# VirtualKeyBoradMouse_2020-04-23_12-54-09.net
KiCad netlist of a schematic drawn in Altium Designer
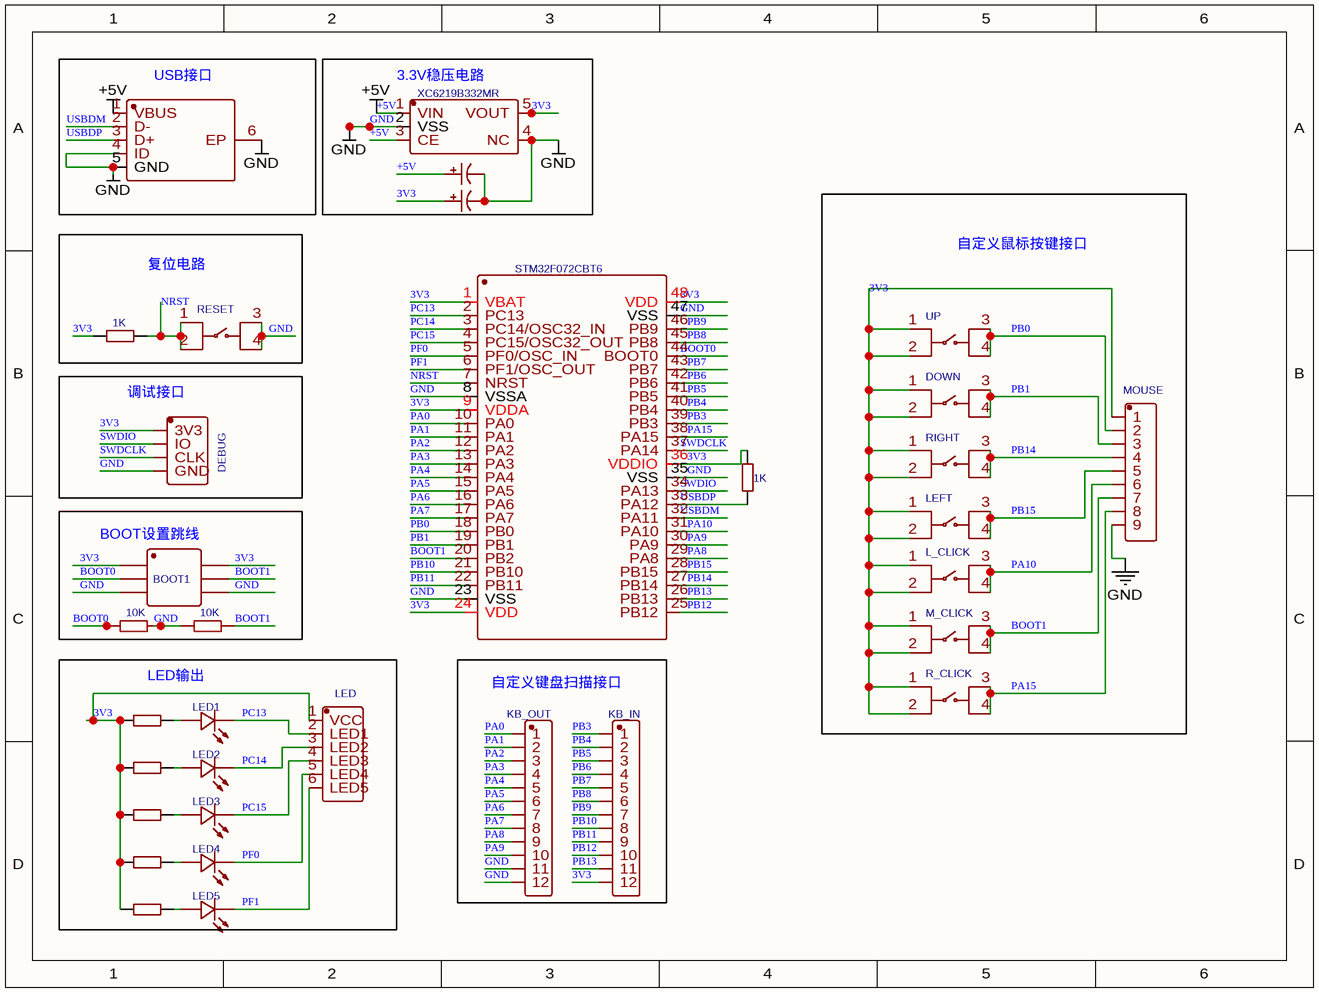
[diagram p0: VirtualKeyBoradMouse_2020-04-23_12-54-09.schdoc]

(export (version "E")
  (design (tool "Eeschema 10.0.6"))
  (components
    (comp (ref "BOOT1")
      (value "210S-2*3P L=11.6MMGold-plated black")
      (fields (field (name "BOM_SUPPLIER PART") "C124384") (field (name "CONTRIBUTOR") "LCSC"))
      (libsource (lib "altium-import") (part "root_0_210S-2*3P L=11.6MMGold-plated black_"))
    )
    (comp (ref "C1")
      (value "100uF")
      (fields
        (field (name "BOM_MANUFACTURER PART") "RVT1A101M0505")
        (field (name "BOM_SUPPLIER PART") "C3347")
      )
      (libsource (lib "altium-import") (part "root_1_100uF_"))
    )
    (comp (ref "C2")
      (value "100uF")
      (fields
        (field (name "BOM_MANUFACTURER PART") "RVT1A101M0505")
        (field (name "BOM_SUPPLIER PART") "C3347")
      )
      (libsource (lib "altium-import") (part "root_1_100uF_"))
    )
    (comp (ref "DEBUG")
      (value "MTP125-1104S1")
      (fields (field (name "BOM_SUPPLIER PART") "C358686") (field (name "CONTRIBUTOR") "LCSC"))
      (libsource (lib "altium-import") (part "root_0_MTP125-1104S1_"))
    )
    (comp (ref "DOWN")
      (value "K2-6639SP-C4SC-04")
      (fields (field (name "BOM_SUPPLIER PART") "C83206"))
      (libsource (lib "altium-import") (part "root_0_K2-6639SP-C4SC-04_"))
    )
    (comp (ref "KB_IN")
      (value "C247920")
      (fields (field (name "CONTRIBUTOR") "LCSC"))
      (libsource (lib "altium-import") (part "root_0_C247920_"))
    )
    (comp (ref "KB_OUT")
      (value "C247920")
      (fields (field (name "CONTRIBUTOR") "LCSC"))
      (libsource (lib "altium-import") (part "root_0_C247920_"))
    )
    (comp (ref "LED")
      (value "210S-1*6P L=11.6MMGold-plated black")
      (fields (field (name "BOM_SUPPLIER PART") "C124380") (field (name "CONTRIBUTOR") "LCSC"))
      (libsource (lib "altium-import") (part "root_0_210S-1*6P L=11.6MMGold-plated black_"))
    )
    (comp (ref "LED1")
      (value "NCD0603R5")
      (fields (field (name "BOM_SUPPLIER PART") "C193902") (field (name "CONTRIBUTOR") "LCSC"))
      (libsource (lib "altium-import") (part "root_2_NCD0603R5_"))
    )
    (comp (ref "LED2")
      (value "NCD0603R5")
      (fields (field (name "BOM_SUPPLIER PART") "C193902") (field (name "CONTRIBUTOR") "LCSC"))
      (libsource (lib "altium-import") (part "root_2_NCD0603R5_"))
    )
    (comp (ref "LED3")
      (value "NCD0603R5")
      (fields (field (name "BOM_SUPPLIER PART") "C193902") (field (name "CONTRIBUTOR") "LCSC"))
      (libsource (lib "altium-import") (part "root_2_NCD0603R5_"))
    )
    (comp (ref "LED4")
      (value "NCD0603R5")
      (fields (field (name "BOM_SUPPLIER PART") "C193902") (field (name "CONTRIBUTOR") "LCSC"))
      (libsource (lib "altium-import") (part "root_2_NCD0603R5_"))
    )
    (comp (ref "LED5")
      (value "NCD0603R5")
      (fields (field (name "BOM_SUPPLIER PART") "C193902") (field (name "CONTRIBUTOR") "LCSC"))
      (libsource (lib "altium-import") (part "root_2_NCD0603R5_"))
    )
    (comp (ref "LEFT")
      (value "K2-6639SP-C4SC-04")
      (fields (field (name "BOM_SUPPLIER PART") "C83206"))
      (libsource (lib "altium-import") (part "root_0_K2-6639SP-C4SC-04_"))
    )
    (comp (ref "L_CLICK")
      (value "K2-6639SP-C4SC-04")
      (fields (field (name "BOM_SUPPLIER PART") "C83206"))
      (libsource (lib "altium-import") (part "root_0_K2-6639SP-C4SC-04_"))
    )
    (comp (ref "MOUSE")
      (value "220S-1*9P H=8.5MM Ytype Gold-plated")
      (fields (field (name "BOM_SUPPLIER PART") "C124417") (field (name "CONTRIBUTOR") "LCSC"))
      (libsource (lib "altium-import") (part "root_0_220S-1*9P H=8.5MM Ytype Gold-plated_"))
    )
    (comp (ref "M_CLICK")
      (value "K2-6639SP-C4SC-04")
      (fields (field (name "BOM_SUPPLIER PART") "C83206"))
      (libsource (lib "altium-import") (part "root_0_K2-6639SP-C4SC-04_"))
    )
    (comp (ref "R1")
      (value "1K")
      (fields
        (field (name "BOM_MANUFACTURER PART") "0603WAF1001T5E")
        (field (name "BOM_SUPPLIER PART") "C21190")
      )
      (libsource (lib "altium-import") (part "root_1_1K_"))
    )
    (comp (ref "R2")
      (value "1K")
      (fields
        (field (name "BOM_MANUFACTURER PART") "0603WAF1001T5E")
        (field (name "BOM_SUPPLIER PART") "C21190")
      )
      (libsource (lib "altium-import") (part "root_0_1K_"))
    )
    (comp (ref "R3")
      (value "10K")
      (fields
        (field (name "BOM_SUPPLIER PART") "C237800")
        (field (name "BOM_MANUFACTURER PART") "RMCF1206JT10K0")
        (field (name "CONTRIBUTOR") "LCSC")
      )
      (libsource (lib "altium-import") (part "root_0_10K_"))
    )
    (comp (ref "R4")
      (value "10K")
      (fields
        (field (name "BOM_SUPPLIER PART") "C237800")
        (field (name "BOM_MANUFACTURER PART") "RMCF1206JT10K0")
        (field (name "CONTRIBUTOR") "LCSC")
      )
      (libsource (lib "altium-import") (part "root_0_10K_"))
    )
    (comp (ref "R5")
      (value "470")
      (fields
        (field (name "BOM_MANUFACTURER PART") "RTT03471JTP")
        (field (name "BOM_SUPPLIER PART") "C103661")
      )
      (libsource (lib "altium-import") (part "root_0_470_"))
    )
    (comp (ref "R6")
      (value "470")
      (fields
        (field (name "BOM_MANUFACTURER PART") "RTT03471JTP")
        (field (name "BOM_SUPPLIER PART") "C103661")
      )
      (libsource (lib "altium-import") (part "root_0_470_"))
    )
    (comp (ref "R7")
      (value "470")
      (fields
        (field (name "BOM_MANUFACTURER PART") "RTT03471JTP")
        (field (name "BOM_SUPPLIER PART") "C103661")
      )
      (libsource (lib "altium-import") (part "root_0_470_"))
    )
    (comp (ref "R8")
      (value "470")
      (fields
        (field (name "BOM_MANUFACTURER PART") "RTT03471JTP")
        (field (name "BOM_SUPPLIER PART") "C103661")
      )
      (libsource (lib "altium-import") (part "root_0_470_"))
    )
    (comp (ref "R9")
      (value "470")
      (fields
        (field (name "BOM_MANUFACTURER PART") "RTT03471JTP")
        (field (name "BOM_SUPPLIER PART") "C103661")
      )
      (libsource (lib "altium-import") (part "root_0_470_"))
    )
    (comp (ref "RESET")
      (value "K2-6639SP-C4SC-04")
      (fields (field (name "BOM_SUPPLIER PART") "C83206"))
      (libsource (lib "altium-import") (part "root_0_K2-6639SP-C4SC-04_"))
    )
    (comp (ref "RIGHT")
      (value "K2-6639SP-C4SC-04")
      (fields (field (name "BOM_SUPPLIER PART") "C83206"))
      (libsource (lib "altium-import") (part "root_0_K2-6639SP-C4SC-04_"))
    )
    (comp (ref "R_CLICK")
      (value "K2-6639SP-C4SC-04")
      (fields (field (name "BOM_SUPPLIER PART") "C83206"))
      (libsource (lib "altium-import") (part "root_0_K2-6639SP-C4SC-04_"))
    )
    (comp (ref "U1")
      (value "STM32F072CBT6")
      (fields (field (name "BOM_SUPPLIER PART") "C81720"))
      (libsource (lib "altium-import") (part "root_0_STM32F072CBT6_"))
    )
    (comp (ref "U2")
      (value "XC6219B332MR")
      (fields (field (name "BOM_SUPPLIER PART") "C46517"))
      (libsource (lib "altium-import") (part "root_0_XC6219B332MR_"))
    )
    (comp (ref "UP")
      (value "K2-6639SP-C4SC-04")
      (fields (field (name "BOM_SUPPLIER PART") "C83206"))
      (libsource (lib "altium-import") (part "root_0_K2-6639SP-C4SC-04_"))
    )
    (comp (ref "USB1")
      (value "67503-1020")
      (fields (field (name "BOM_SUPPLIER PART") "C136451") (field (name "CONTRIBUTOR") "LCSC"))
      (libsource (lib "altium-import") (part "root_0_67503-1020_"))
    )
  )
  (nets
    (net (code "1") (name "+5V") (class "Default")
      (node (ref "C2") (pin "1") (pinfunction "1_1") (pintype "passive"))
      (node (ref "U2") (pin "1") (pinfunction "VIN_1") (pintype "passive"))
      (node (ref "U2") (pin "3") (pinfunction "CE_3") (pintype "passive"))
      (node (ref "USB1") (pin "1") (pinfunction "VBUS_1") (pintype "passive"))
    )
    (net (code "2") (name "/3V3") (class "Default")
      (node (ref "BOOT1") (pin "1") (pinfunction "1_1") (pintype "passive"))
      (node (ref "BOOT1") (pin "2") (pinfunction "2_2") (pintype "passive"))
      (node (ref "C1") (pin "1") (pinfunction "1_1") (pintype "passive"))
      (node (ref "DEBUG") (pin "1") (pinfunction "3V3_1") (pintype "passive"))
      (node (ref "DOWN") (pin "1") (pinfunction "1_1") (pintype "passive"))
      (node (ref "DOWN") (pin "2") (pinfunction "2_2") (pintype "passive"))
      (node (ref "KB_IN") (pin "12") (pinfunction "12_12") (pintype "passive"))
      (node (ref "LED") (pin "1") (pinfunction "VCC_1") (pintype "passive"))
      (node (ref "LEFT") (pin "1") (pinfunction "1_1") (pintype "passive"))
      (node (ref "LEFT") (pin "2") (pinfunction "2_2") (pintype "passive"))
      (node (ref "L_CLICK") (pin "1") (pinfunction "1_1") (pintype "passive"))
      (node (ref "L_CLICK") (pin "2") (pinfunction "2_2") (pintype "passive"))
      (node (ref "MOUSE") (pin "1") (pinfunction "1_1") (pintype "passive"))
      (node (ref "M_CLICK") (pin "1") (pinfunction "1_1") (pintype "passive"))
      (node (ref "M_CLICK") (pin "2") (pinfunction "2_2") (pintype "passive"))
      (node (ref "R1") (pin "2") (pinfunction "2_2") (pintype "passive"))
      (node (ref "R2") (pin "1") (pinfunction "1_1") (pintype "passive"))
      (node (ref "R5") (pin "1") (pinfunction "1_1") (pintype "passive"))
      (node (ref "R6") (pin "1") (pinfunction "1_1") (pintype "passive"))
      (node (ref "R7") (pin "1") (pinfunction "1_1") (pintype "passive"))
      (node (ref "R8") (pin "1") (pinfunction "1_1") (pintype "passive"))
      (node (ref "R9") (pin "1") (pinfunction "1_1") (pintype "passive"))
      (node (ref "RIGHT") (pin "1") (pinfunction "1_1") (pintype "passive"))
      (node (ref "RIGHT") (pin "2") (pinfunction "2_2") (pintype "passive"))
      (node (ref "R_CLICK") (pin "1") (pinfunction "1_1") (pintype "passive"))
      (node (ref "R_CLICK") (pin "2") (pinfunction "2_2") (pintype "passive"))
      (node (ref "U1") (pin "1") (pinfunction "VBAT_1") (pintype "passive"))
      (node (ref "U1") (pin "24") (pinfunction "VDD_24") (pintype "passive"))
      (node (ref "U1") (pin "36") (pinfunction "VDDIO_36") (pintype "passive"))
      (node (ref "U1") (pin "48") (pinfunction "VDD_48") (pintype "passive"))
      (node (ref "U1") (pin "9") (pinfunction "VDDA_9") (pintype "passive"))
      (node (ref "U2") (pin "5") (pinfunction "VOUT_5") (pintype "passive"))
      (node (ref "UP") (pin "1") (pinfunction "1_1") (pintype "passive"))
      (node (ref "UP") (pin "2") (pinfunction "2_2") (pintype "passive"))
    )
    (net (code "3") (name "/BOOT0") (class "Default")
      (node (ref "BOOT1") (pin "3") (pinfunction "3_3") (pintype "passive"))
      (node (ref "R3") (pin "1") (pinfunction "1_1") (pintype "passive"))
      (node (ref "U1") (pin "44") (pinfunction "BOOT0_44") (pintype "passive"))
    )
    (net (code "4") (name "/BOOT1") (class "Default")
      (node (ref "BOOT1") (pin "4") (pinfunction "4_4") (pintype "passive"))
      (node (ref "MOUSE") (pin "7") (pinfunction "7_7") (pintype "passive"))
      (node (ref "M_CLICK") (pin "3") (pinfunction "3_3") (pintype "passive"))
      (node (ref "M_CLICK") (pin "4") (pinfunction "4_4") (pintype "passive"))
      (node (ref "R4") (pin "2") (pinfunction "2_2") (pintype "passive"))
      (node (ref "U1") (pin "20") (pinfunction "PB2_20") (pintype "passive"))
    )
    (net (code "5") (name "/NRST") (class "Default")
      (node (ref "R2") (pin "2") (pinfunction "2_2") (pintype "passive"))
      (node (ref "RESET") (pin "1") (pinfunction "1_1") (pintype "passive"))
      (node (ref "RESET") (pin "2") (pinfunction "2_2") (pintype "passive"))
      (node (ref "U1") (pin "7") (pinfunction "NRST_7") (pintype "passive"))
    )
    (net (code "6") (name "/PA0") (class "Default")
      (node (ref "KB_OUT") (pin "1") (pinfunction "1_1") (pintype "passive"))
      (node (ref "U1") (pin "10") (pinfunction "PA0_10") (pintype "passive"))
    )
    (net (code "7") (name "/PA1") (class "Default")
      (node (ref "KB_OUT") (pin "2") (pinfunction "2_2") (pintype "passive"))
      (node (ref "U1") (pin "11") (pinfunction "PA1_11") (pintype "passive"))
    )
    (net (code "8") (name "/PA2") (class "Default")
      (node (ref "KB_OUT") (pin "3") (pinfunction "3_3") (pintype "passive"))
      (node (ref "U1") (pin "12") (pinfunction "PA2_12") (pintype "passive"))
    )
    (net (code "9") (name "/PA3") (class "Default")
      (node (ref "KB_OUT") (pin "4") (pinfunction "4_4") (pintype "passive"))
      (node (ref "U1") (pin "13") (pinfunction "PA3_13") (pintype "passive"))
    )
    (net (code "10") (name "/PA4") (class "Default")
      (node (ref "KB_OUT") (pin "5") (pinfunction "5_5") (pintype "passive"))
      (node (ref "U1") (pin "14") (pinfunction "PA4_14") (pintype "passive"))
    )
    (net (code "11") (name "/PA5") (class "Default")
      (node (ref "KB_OUT") (pin "6") (pinfunction "6_6") (pintype "passive"))
      (node (ref "U1") (pin "15") (pinfunction "PA5_15") (pintype "passive"))
    )
    (net (code "12") (name "/PA6") (class "Default")
      (node (ref "KB_OUT") (pin "7") (pinfunction "7_7") (pintype "passive"))
      (node (ref "U1") (pin "16") (pinfunction "PA6_16") (pintype "passive"))
    )
    (net (code "13") (name "/PA7") (class "Default")
      (node (ref "KB_OUT") (pin "8") (pinfunction "8_8") (pintype "passive"))
      (node (ref "U1") (pin "17") (pinfunction "PA7_17") (pintype "passive"))
    )
    (net (code "14") (name "/PA8") (class "Default")
      (node (ref "KB_OUT") (pin "9") (pinfunction "9_9") (pintype "passive"))
      (node (ref "U1") (pin "29") (pinfunction "PA8_29") (pintype "passive"))
    )
    (net (code "15") (name "/PA9") (class "Default")
      (node (ref "KB_OUT") (pin "10") (pinfunction "10_10") (pintype "passive"))
      (node (ref "U1") (pin "30") (pinfunction "PA9_30") (pintype "passive"))
    )
    (net (code "16") (name "/PA10") (class "Default")
      (node (ref "L_CLICK") (pin "3") (pinfunction "3_3") (pintype "passive"))
      (node (ref "L_CLICK") (pin "4") (pinfunction "4_4") (pintype "passive"))
      (node (ref "MOUSE") (pin "6") (pinfunction "6_6") (pintype "passive"))
      (node (ref "U1") (pin "31") (pinfunction "PA10_31") (pintype "passive"))
    )
    (net (code "17") (name "/PA15") (class "Default")
      (node (ref "MOUSE") (pin "8") (pinfunction "8_8") (pintype "passive"))
      (node (ref "R_CLICK") (pin "3") (pinfunction "3_3") (pintype "passive"))
      (node (ref "R_CLICK") (pin "4") (pinfunction "4_4") (pintype "passive"))
      (node (ref "U1") (pin "38") (pinfunction "PA15_38") (pintype "passive"))
    )
    (net (code "18") (name "/PB0") (class "Default")
      (node (ref "MOUSE") (pin "2") (pinfunction "2_2") (pintype "passive"))
      (node (ref "U1") (pin "18") (pinfunction "PB0_18") (pintype "passive"))
      (node (ref "UP") (pin "3") (pinfunction "3_3") (pintype "passive"))
      (node (ref "UP") (pin "4") (pinfunction "4_4") (pintype "passive"))
    )
    (net (code "19") (name "/PB1") (class "Default")
      (node (ref "DOWN") (pin "3") (pinfunction "3_3") (pintype "passive"))
      (node (ref "DOWN") (pin "4") (pinfunction "4_4") (pintype "passive"))
      (node (ref "MOUSE") (pin "3") (pinfunction "3_3") (pintype "passive"))
      (node (ref "U1") (pin "19") (pinfunction "PB1_19") (pintype "passive"))
    )
    (net (code "20") (name "/PB3") (class "Default")
      (node (ref "KB_IN") (pin "1") (pinfunction "1_1") (pintype "passive"))
      (node (ref "U1") (pin "39") (pinfunction "PB3_39") (pintype "passive"))
    )
    (net (code "21") (name "/PB4") (class "Default")
      (node (ref "KB_IN") (pin "2") (pinfunction "2_2") (pintype "passive"))
      (node (ref "U1") (pin "40") (pinfunction "PB4_40") (pintype "passive"))
    )
    (net (code "22") (name "/PB5") (class "Default")
      (node (ref "KB_IN") (pin "3") (pinfunction "3_3") (pintype "passive"))
      (node (ref "U1") (pin "41") (pinfunction "PB5_41") (pintype "passive"))
    )
    (net (code "23") (name "/PB6") (class "Default")
      (node (ref "KB_IN") (pin "4") (pinfunction "4_4") (pintype "passive"))
      (node (ref "U1") (pin "42") (pinfunction "PB6_42") (pintype "passive"))
    )
    (net (code "24") (name "/PB7") (class "Default")
      (node (ref "KB_IN") (pin "5") (pinfunction "5_5") (pintype "passive"))
      (node (ref "U1") (pin "43") (pinfunction "PB7_43") (pintype "passive"))
    )
    (net (code "25") (name "/PB8") (class "Default")
      (node (ref "KB_IN") (pin "6") (pinfunction "6_6") (pintype "passive"))
      (node (ref "U1") (pin "45") (pinfunction "PB8_45") (pintype "passive"))
    )
    (net (code "26") (name "/PB9") (class "Default")
      (node (ref "KB_IN") (pin "7") (pinfunction "7_7") (pintype "passive"))
      (node (ref "U1") (pin "46") (pinfunction "PB9_46") (pintype "passive"))
    )
    (net (code "27") (name "/PB10") (class "Default")
      (node (ref "KB_IN") (pin "8") (pinfunction "8_8") (pintype "passive"))
      (node (ref "U1") (pin "21") (pinfunction "PB10_21") (pintype "passive"))
    )
    (net (code "28") (name "/PB11") (class "Default")
      (node (ref "KB_IN") (pin "9") (pinfunction "9_9") (pintype "passive"))
      (node (ref "U1") (pin "22") (pinfunction "PB11_22") (pintype "passive"))
    )
    (net (code "29") (name "/PB12") (class "Default")
      (node (ref "KB_IN") (pin "10") (pinfunction "10_10") (pintype "passive"))
      (node (ref "U1") (pin "25") (pinfunction "PB12_25") (pintype "passive"))
    )
    (net (code "30") (name "/PB13") (class "Default")
      (node (ref "KB_IN") (pin "11") (pinfunction "11_11") (pintype "passive"))
      (node (ref "U1") (pin "26") (pinfunction "PB13_26") (pintype "passive"))
    )
    (net (code "31") (name "/PB14") (class "Default")
      (node (ref "MOUSE") (pin "4") (pinfunction "4_4") (pintype "passive"))
      (node (ref "RIGHT") (pin "3") (pinfunction "3_3") (pintype "passive"))
      (node (ref "RIGHT") (pin "4") (pinfunction "4_4") (pintype "passive"))
      (node (ref "U1") (pin "27") (pinfunction "PB14_27") (pintype "passive"))
    )
    (net (code "32") (name "/PB15") (class "Default")
      (node (ref "LEFT") (pin "3") (pinfunction "3_3") (pintype "passive"))
      (node (ref "LEFT") (pin "4") (pinfunction "4_4") (pintype "passive"))
      (node (ref "MOUSE") (pin "5") (pinfunction "5_5") (pintype "passive"))
      (node (ref "U1") (pin "28") (pinfunction "PB15_28") (pintype "passive"))
    )
    (net (code "33") (name "/PC13") (class "Default")
      (node (ref "LED") (pin "2") (pinfunction "LED1_2") (pintype "passive"))
      (node (ref "LED1") (pin "1") (pinfunction "-_1") (pintype "passive"))
      (node (ref "U1") (pin "2") (pinfunction "PC13_2") (pintype "passive"))
    )
    (net (code "34") (name "/PC14") (class "Default")
      (node (ref "LED") (pin "3") (pinfunction "LED2_3") (pintype "passive"))
      (node (ref "LED2") (pin "1") (pinfunction "-_1") (pintype "passive"))
      (node (ref "U1") (pin "3") (pinfunction "PC14/OSC32_IN_3") (pintype "passive"))
    )
    (net (code "35") (name "/PC15") (class "Default")
      (node (ref "LED") (pin "4") (pinfunction "LED3_4") (pintype "passive"))
      (node (ref "LED3") (pin "1") (pinfunction "-_1") (pintype "passive"))
      (node (ref "U1") (pin "4") (pinfunction "PC15/OSC32_OUT_4") (pintype "passive"))
    )
    (net (code "36") (name "/PF0") (class "Default")
      (node (ref "LED") (pin "5") (pinfunction "LED4_5") (pintype "passive"))
      (node (ref "LED4") (pin "1") (pinfunction "-_1") (pintype "passive"))
      (node (ref "U1") (pin "5") (pinfunction "PF0/OSC_IN_5") (pintype "passive"))
    )
    (net (code "37") (name "/PF1") (class "Default")
      (node (ref "LED") (pin "6") (pinfunction "LED5_6") (pintype "passive"))
      (node (ref "LED5") (pin "1") (pinfunction "-_1") (pintype "passive"))
      (node (ref "U1") (pin "6") (pinfunction "PF1/OSC_OUT_6") (pintype "passive"))
    )
    (net (code "38") (name "/SWDCLK") (class "Default")
      (node (ref "DEBUG") (pin "3") (pinfunction "CLK_3") (pintype "passive"))
      (node (ref "U1") (pin "37") (pinfunction "PA14_37") (pintype "passive"))
    )
    (net (code "39") (name "/SWDIO") (class "Default")
      (node (ref "DEBUG") (pin "2") (pinfunction "IO_2") (pintype "passive"))
      (node (ref "U1") (pin "34") (pinfunction "PA13_34") (pintype "passive"))
    )
    (net (code "40") (name "/USBDM") (class "Default")
      (node (ref "U1") (pin "32") (pinfunction "PA11_32") (pintype "passive"))
      (node (ref "USB1") (pin "2") (pinfunction "D-_2") (pintype "passive"))
    )
    (net (code "41") (name "/USBDP") (class "Default")
      (node (ref "R1") (pin "1") (pinfunction "1_1") (pintype "passive"))
      (node (ref "U1") (pin "33") (pinfunction "PA12_33") (pintype "passive"))
      (node (ref "USB1") (pin "3") (pinfunction "D+_3") (pintype "passive"))
    )
    (net (code "42") (name "GND") (class "Default")
      (node (ref "BOOT1") (pin "5") (pinfunction "5_5") (pintype "passive"))
      (node (ref "BOOT1") (pin "6") (pinfunction "6_6") (pintype "passive"))
      (node (ref "C1") (pin "2") (pinfunction "2_2") (pintype "passive"))
      (node (ref "C2") (pin "2") (pinfunction "2_2") (pintype "passive"))
      (node (ref "DEBUG") (pin "4") (pinfunction "GND_4") (pintype "passive"))
      (node (ref "KB_OUT") (pin "11") (pinfunction "11_11") (pintype "passive"))
      (node (ref "KB_OUT") (pin "12") (pinfunction "12_12") (pintype "passive"))
      (node (ref "MOUSE") (pin "9") (pinfunction "9_9") (pintype "passive"))
      (node (ref "R3") (pin "2") (pinfunction "2_2") (pintype "passive"))
      (node (ref "R4") (pin "1") (pinfunction "1_1") (pintype "passive"))
      (node (ref "RESET") (pin "3") (pinfunction "3_3") (pintype "passive"))
      (node (ref "RESET") (pin "4") (pinfunction "4_4") (pintype "passive"))
      (node (ref "U1") (pin "23") (pinfunction "VSS_23") (pintype "passive"))
      (node (ref "U1") (pin "35") (pinfunction "VSS_35") (pintype "passive"))
      (node (ref "U1") (pin "47") (pinfunction "VSS_47") (pintype "passive"))
      (node (ref "U1") (pin "8") (pinfunction "VSSA_8") (pintype "passive"))
      (node (ref "U2") (pin "2") (pinfunction "VSS_2") (pintype "passive"))
      (node (ref "U2") (pin "4") (pinfunction "NC_4") (pintype "passive"))
      (node (ref "USB1") (pin "4") (pinfunction "ID_4") (pintype "passive"))
      (node (ref "USB1") (pin "5") (pinfunction "GND_5") (pintype "passive"))
      (node (ref "USB1") (pin "6") (pinfunction "EP_6") (pintype "passive"))
    )
    (net (code "43") (name "Net-(LED1-+)") (class "Default")
      (node (ref "LED1") (pin "2") (pinfunction "+_2") (pintype "passive"))
      (node (ref "R5") (pin "2") (pinfunction "2_2") (pintype "passive"))
    )
    (net (code "44") (name "Net-(LED2-+)") (class "Default")
      (node (ref "LED2") (pin "2") (pinfunction "+_2") (pintype "passive"))
      (node (ref "R6") (pin "2") (pinfunction "2_2") (pintype "passive"))
    )
    (net (code "45") (name "Net-(LED3-+)") (class "Default")
      (node (ref "LED3") (pin "2") (pinfunction "+_2") (pintype "passive"))
      (node (ref "R7") (pin "2") (pinfunction "2_2") (pintype "passive"))
    )
    (net (code "46") (name "Net-(LED4-+)") (class "Default")
      (node (ref "LED4") (pin "2") (pinfunction "+_2") (pintype "passive"))
      (node (ref "R8") (pin "2") (pinfunction "2_2") (pintype "passive"))
    )
    (net (code "47") (name "Net-(LED5-+)") (class "Default")
      (node (ref "LED5") (pin "2") (pinfunction "+_2") (pintype "passive"))
      (node (ref "R9") (pin "2") (pinfunction "2_2") (pintype "passive"))
    )
  )
)
